# Flash.net
KiCad netlist of a schematic drawn in Altium Designer
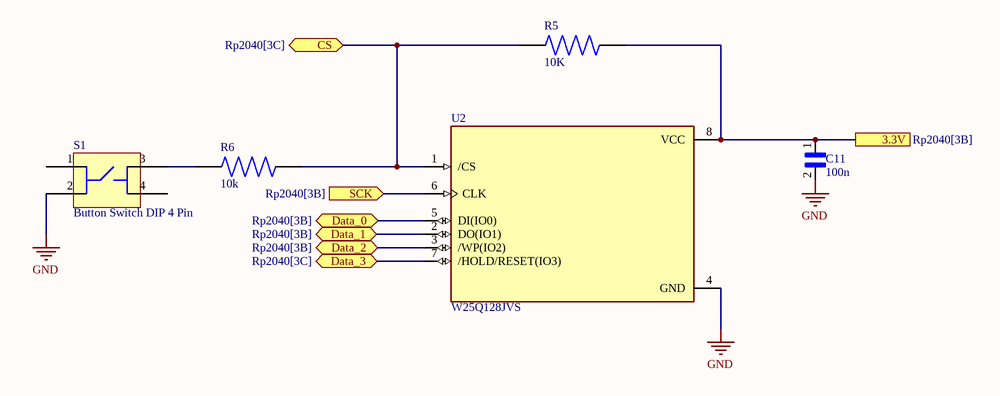
[diagram p0: Flash.SchDoc]

(export (version "E")
  (design (tool "Eeschema 10.0.6"))
  (components
    (comp (ref "C11")
      (value "100n")
      (footprint "SMD Capacator")
      (libsource (lib "Basic") (part "SMD Capacator"))
    )
    (comp (ref "R5") (value "10K") (footprint "SMD Resistor") (libsource (lib "Basic") (part "SMD Resistor")))
    (comp (ref "R6") (value "10k") (footprint "SMD Resistor") (libsource (lib "Basic") (part "SMD Resistor")))
    (comp (ref "S1")
      (value "Button Switch DIP 4 Pin")
      (footprint "Button Switch DIP 4 Pin")
      (libsource (lib "Basic") (part "Button Switch DIP 4 Pin"))
    )
    (comp (ref "U2")
      (value "W25Q128JVS")
      (footprint "W25Q128JVS")
      (libsource (lib "Basic") (part "W25Q128JVS"))
    )
  )
  (nets
    (net (code "1") (name "/3.3V") (class "Default")
      (node (ref "C11") (pin "1") (pinfunction "1_1") (pintype "passive"))
      (node (ref "R5") (pin "2") (pinfunction "2_2") (pintype "passive"))
      (node (ref "U2") (pin "8") (pinfunction "VCC_8") (pintype "power_in"))
    )
    (net (code "2") (name "/CS") (class "Default")
      (node (ref "R5") (pin "1") (pinfunction "1_1") (pintype "passive"))
      (node (ref "R6") (pin "2") (pinfunction "2_2") (pintype "passive"))
      (node (ref "U2") (pin "1") (pinfunction "/CS_1") (pintype "input"))
    )
    (net (code "3") (name "/Data_0") (class "Default")
      (node (ref "U2") (pin "5") (pinfunction "DI(IO0)_5") (pintype "bidirectional"))
    )
    (net (code "4") (name "/Data_1") (class "Default")
      (node (ref "U2") (pin "2") (pinfunction "DO(IO1)_2") (pintype "bidirectional"))
    )
    (net (code "5") (name "/Data_2") (class "Default")
      (node (ref "U2") (pin "3") (pinfunction "/WP(IO2)_3") (pintype "bidirectional"))
    )
    (net (code "6") (name "/Data_3") (class "Default")
      (node (ref "U2") (pin "7") (pinfunction "/HOLD/RESET(IO3)_7") (pintype "bidirectional"))
    )
    (net (code "7") (name "/SCK") (class "Default")
      (node (ref "U2") (pin "6") (pinfunction "CLK_6") (pintype "input"))
    )
    (net (code "8") (name "GND") (class "Default")
      (node (ref "C11") (pin "2") (pinfunction "2_2") (pintype "passive"))
      (node (ref "S1") (pin "2") (pinfunction "2_2") (pintype "passive"))
      (node (ref "U2") (pin "4") (pinfunction "GND_4") (pintype "power_in"))
    )
    (net (code "9") (name "Net-(R6-Pad1)") (class "Default")
      (node (ref "R6") (pin "1") (pinfunction "1_1") (pintype "passive"))
      (node (ref "S1") (pin "3") (pinfunction "3_3") (pintype "passive"))
    )
    (net (code "10") (name "unconnected-(S1-Pad1)") (class "Default")
      (node (ref "S1") (pin "1") (pinfunction "1_1") (pintype "passive"))
    )
    (net (code "11") (name "unconnected-(S1-Pad4)") (class "Default")
      (node (ref "S1") (pin "4") (pinfunction "4_4") (pintype "passive"))
    )
  )
)
